# card_base.net
KiCad netlist of a schematic drawn in EAGLE
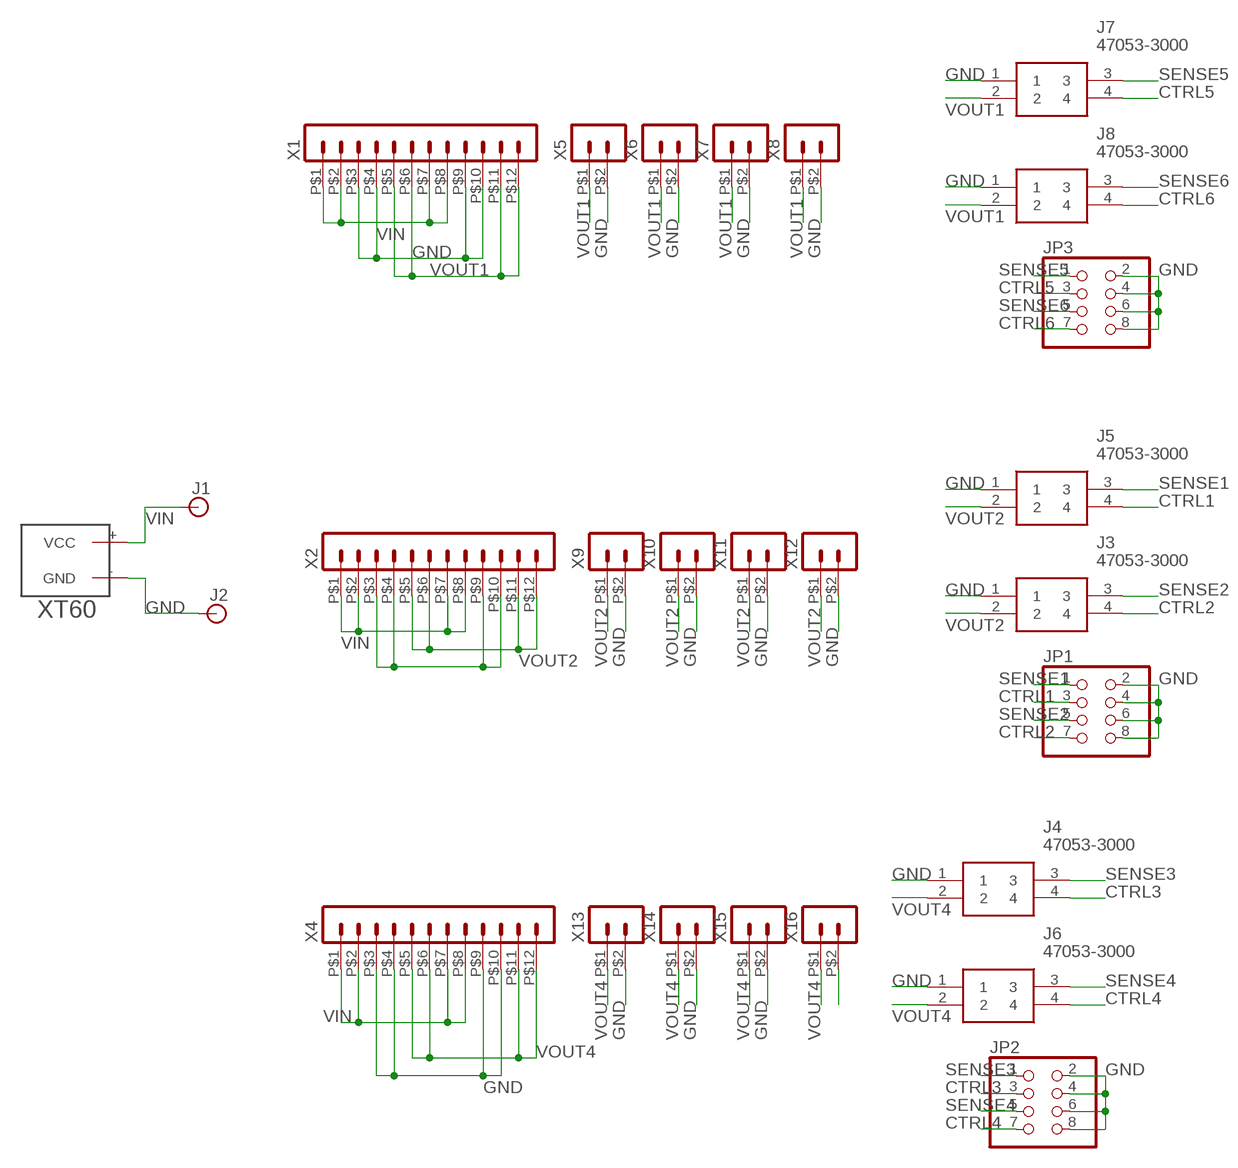
[diagram p0: schematic, sheet 1]

(export (version "E")
  (design (tool "Eeschema 10.0.6"))
  (components
    (comp (ref "J1")
      (value "BANANA_CONN")
      (footprint "eagle-import:BANANA_CONN")
      (libsource (lib "eagle-import") (part "BANANA_CONN"))
    )
    (comp (ref "J2")
      (value "BANANA_CONN")
      (footprint "eagle-import:BANANA_CONN")
      (libsource (lib "eagle-import") (part "BANANA_CONN"))
    )
    (comp (ref "J3")
      (value "47053-3000")
      (footprint "eagle-import:470533000")
      (fields (field (name "MOUSER_PART_NUMBER") "538-47053-3000"))
      (libsource (lib "eagle-import") (part "47053-3000"))
    )
    (comp (ref "J4")
      (value "47053-3000")
      (footprint "eagle-import:470533000")
      (fields (field (name "MOUSER_PART_NUMBER") "538-47053-3000"))
      (libsource (lib "eagle-import") (part "47053-3000"))
    )
    (comp (ref "J5")
      (value "47053-3000")
      (footprint "eagle-import:470533000")
      (fields (field (name "MOUSER_PART_NUMBER") "538-47053-3000"))
      (libsource (lib "eagle-import") (part "47053-3000"))
    )
    (comp (ref "J6")
      (value "47053-3000")
      (footprint "eagle-import:470533000")
      (fields (field (name "MOUSER_PART_NUMBER") "538-47053-3000"))
      (libsource (lib "eagle-import") (part "47053-3000"))
    )
    (comp (ref "J7")
      (value "47053-3000")
      (footprint "eagle-import:470533000")
      (fields (field (name "MOUSER_PART_NUMBER") "538-47053-3000"))
      (libsource (lib "eagle-import") (part "47053-3000"))
    )
    (comp (ref "J8")
      (value "47053-3000")
      (footprint "eagle-import:470533000")
      (fields (field (name "MOUSER_PART_NUMBER") "538-47053-3000"))
      (libsource (lib "eagle-import") (part "47053-3000"))
    )
    (comp (ref "JP1")
      (value "PINHD-2X4")
      (footprint "eagle-import:2X04")
      (libsource (lib "eagle-import") (part "PINHD-2X4"))
    )
    (comp (ref "JP2")
      (value "PINHD-2X4")
      (footprint "eagle-import:2X04")
      (libsource (lib "eagle-import") (part "PINHD-2X4"))
    )
    (comp (ref "JP3")
      (value "PINHD-2X4")
      (footprint "eagle-import:2X04")
      (libsource (lib "eagle-import") (part "PINHD-2X4"))
    )
    (comp (ref "U$1")
      (value "XT60")
      (footprint "eagle-import:XT60")
      (libsource (lib "eagle-import") (part "XT60"))
    )
    (comp (ref "X1")
      (value "HEADER_POS12_44432-1201")
      (footprint "eagle-import:44432-1201")
      (libsource (lib "eagle-import") (part "HEADER_POS12_?44432-1201"))
    )
    (comp (ref "X2")
      (value "HEADER_POS12_44432-1201")
      (footprint "eagle-import:44432-1201")
      (libsource (lib "eagle-import") (part "HEADER_POS12_?44432-1201"))
    )
    (comp (ref "X4")
      (value "HEADER_POS12_44432-1201")
      (footprint "eagle-import:44432-1201")
      (libsource (lib "eagle-import") (part "HEADER_POS12_?44432-1201"))
    )
    (comp (ref "X5")
      (value "HEADER_POS2_44914-0201")
      (footprint "eagle-import:44914-0201")
      (libsource (lib "eagle-import") (part "HEADER_POS2_?44914-0201"))
    )
    (comp (ref "X6")
      (value "HEADER_POS2_44914-0201")
      (footprint "eagle-import:44914-0201")
      (libsource (lib "eagle-import") (part "HEADER_POS2_?44914-0201"))
    )
    (comp (ref "X7")
      (value "HEADER_POS2_44914-0201")
      (footprint "eagle-import:44914-0201")
      (libsource (lib "eagle-import") (part "HEADER_POS2_?44914-0201"))
    )
    (comp (ref "X8")
      (value "HEADER_POS2_44914-0201")
      (footprint "eagle-import:44914-0201")
      (libsource (lib "eagle-import") (part "HEADER_POS2_?44914-0201"))
    )
    (comp (ref "X9")
      (value "HEADER_POS2_44914-0201")
      (footprint "eagle-import:44914-0201")
      (libsource (lib "eagle-import") (part "HEADER_POS2_?44914-0201"))
    )
    (comp (ref "X10")
      (value "HEADER_POS2_44914-0201")
      (footprint "eagle-import:44914-0201")
      (libsource (lib "eagle-import") (part "HEADER_POS2_?44914-0201"))
    )
    (comp (ref "X11")
      (value "HEADER_POS2_44914-0201")
      (footprint "eagle-import:44914-0201")
      (libsource (lib "eagle-import") (part "HEADER_POS2_?44914-0201"))
    )
    (comp (ref "X12")
      (value "HEADER_POS2_44914-0201")
      (footprint "eagle-import:44914-0201")
      (libsource (lib "eagle-import") (part "HEADER_POS2_?44914-0201"))
    )
    (comp (ref "X13")
      (value "HEADER_POS2_44914-0201")
      (footprint "eagle-import:44914-0201")
      (libsource (lib "eagle-import") (part "HEADER_POS2_?44914-0201"))
    )
    (comp (ref "X14")
      (value "HEADER_POS2_44914-0201")
      (footprint "eagle-import:44914-0201")
      (libsource (lib "eagle-import") (part "HEADER_POS2_?44914-0201"))
    )
    (comp (ref "X15")
      (value "HEADER_POS2_44914-0201")
      (footprint "eagle-import:44914-0201")
      (libsource (lib "eagle-import") (part "HEADER_POS2_?44914-0201"))
    )
    (comp (ref "X16")
      (value "HEADER_POS2_44914-0201")
      (footprint "eagle-import:44914-0201")
      (libsource (lib "eagle-import") (part "HEADER_POS2_?44914-0201"))
    )
  )
  (nets
    (net (code "1") (name "/CTRL1") (class "Default")
      (node (ref "J5") (pin "4") (pinfunction "4_4") (pintype "bidirectional"))
      (node (ref "JP1") (pin "3") (pinfunction "3_3") (pintype "passive"))
    )
    (net (code "2") (name "/CTRL2") (class "Default")
      (node (ref "J3") (pin "4") (pinfunction "4_4") (pintype "bidirectional"))
      (node (ref "JP1") (pin "7") (pinfunction "7_7") (pintype "passive"))
    )
    (net (code "3") (name "/CTRL3") (class "Default")
      (node (ref "J4") (pin "4") (pinfunction "4_4") (pintype "bidirectional"))
      (node (ref "JP2") (pin "3") (pinfunction "3_3") (pintype "passive"))
    )
    (net (code "4") (name "/CTRL4") (class "Default")
      (node (ref "J6") (pin "4") (pinfunction "4_4") (pintype "bidirectional"))
      (node (ref "JP2") (pin "7") (pinfunction "7_7") (pintype "passive"))
    )
    (net (code "5") (name "/CTRL5") (class "Default")
      (node (ref "J7") (pin "4") (pinfunction "4_4") (pintype "bidirectional"))
      (node (ref "JP3") (pin "3") (pinfunction "3_3") (pintype "passive"))
    )
    (net (code "6") (name "/CTRL6") (class "Default")
      (node (ref "J8") (pin "4") (pinfunction "4_4") (pintype "bidirectional"))
      (node (ref "JP3") (pin "7") (pinfunction "7_7") (pintype "passive"))
    )
    (net (code "7") (name "/GND") (class "Default")
      (node (ref "J2") (pin "P$1") (pinfunction "1_P$1") (pintype "passive"))
      (node (ref "J3") (pin "1") (pinfunction "1_1") (pintype "bidirectional"))
      (node (ref "J4") (pin "1") (pinfunction "1_1") (pintype "bidirectional"))
      (node (ref "J5") (pin "1") (pinfunction "1_1") (pintype "bidirectional"))
      (node (ref "J6") (pin "1") (pinfunction "1_1") (pintype "bidirectional"))
      (node (ref "J7") (pin "1") (pinfunction "1_1") (pintype "bidirectional"))
      (node (ref "J8") (pin "1") (pinfunction "1_1") (pintype "bidirectional"))
      (node (ref "JP1") (pin "2") (pinfunction "2_2") (pintype "passive"))
      (node (ref "JP1") (pin "4") (pinfunction "4_4") (pintype "passive"))
      (node (ref "JP1") (pin "6") (pinfunction "6_6") (pintype "passive"))
      (node (ref "JP1") (pin "8") (pinfunction "8_8") (pintype "passive"))
      (node (ref "JP2") (pin "2") (pinfunction "2_2") (pintype "passive"))
      (node (ref "JP2") (pin "4") (pinfunction "4_4") (pintype "passive"))
      (node (ref "JP2") (pin "6") (pinfunction "6_6") (pintype "passive"))
      (node (ref "JP2") (pin "8") (pinfunction "8_8") (pintype "passive"))
      (node (ref "JP3") (pin "2") (pinfunction "2_2") (pintype "passive"))
      (node (ref "JP3") (pin "4") (pinfunction "4_4") (pintype "passive"))
      (node (ref "JP3") (pin "6") (pinfunction "6_6") (pintype "passive"))
      (node (ref "JP3") (pin "8") (pinfunction "8_8") (pintype "passive"))
      (node (ref "U$1") (pin "-") (pinfunction "GND_-") (pintype "bidirectional"))
      (node (ref "X1") (pin "P$10") (pinfunction "10_P$10") (pintype "passive"))
      (node (ref "X1") (pin "P$3") (pinfunction "3_P$3") (pintype "passive"))
      (node (ref "X1") (pin "P$4") (pinfunction "4_P$4") (pintype "passive"))
      (node (ref "X1") (pin "P$9") (pinfunction "9_P$9") (pintype "passive"))
      (node (ref "X10") (pin "P$2") (pinfunction "2_P$2") (pintype "passive"))
      (node (ref "X11") (pin "P$2") (pinfunction "2_P$2") (pintype "passive"))
      (node (ref "X12") (pin "P$2") (pinfunction "2_P$2") (pintype "passive"))
      (node (ref "X13") (pin "P$2") (pinfunction "2_P$2") (pintype "passive"))
      (node (ref "X14") (pin "P$2") (pinfunction "2_P$2") (pintype "passive"))
      (node (ref "X15") (pin "P$2") (pinfunction "2_P$2") (pintype "passive"))
      (node (ref "X16") (pin "P$2") (pinfunction "2_P$2") (pintype "passive"))
      (node (ref "X2") (pin "P$10") (pinfunction "10_P$10") (pintype "passive"))
      (node (ref "X2") (pin "P$3") (pinfunction "3_P$3") (pintype "passive"))
      (node (ref "X2") (pin "P$4") (pinfunction "4_P$4") (pintype "passive"))
      (node (ref "X2") (pin "P$9") (pinfunction "9_P$9") (pintype "passive"))
      (node (ref "X4") (pin "P$10") (pinfunction "10_P$10") (pintype "passive"))
      (node (ref "X4") (pin "P$3") (pinfunction "3_P$3") (pintype "passive"))
      (node (ref "X4") (pin "P$4") (pinfunction "4_P$4") (pintype "passive"))
      (node (ref "X4") (pin "P$9") (pinfunction "9_P$9") (pintype "passive"))
      (node (ref "X5") (pin "P$2") (pinfunction "2_P$2") (pintype "passive"))
      (node (ref "X6") (pin "P$2") (pinfunction "2_P$2") (pintype "passive"))
      (node (ref "X7") (pin "P$2") (pinfunction "2_P$2") (pintype "passive"))
      (node (ref "X8") (pin "P$2") (pinfunction "2_P$2") (pintype "passive"))
      (node (ref "X9") (pin "P$2") (pinfunction "2_P$2") (pintype "passive"))
    )
    (net (code "8") (name "/SENSE1") (class "Default")
      (node (ref "J5") (pin "3") (pinfunction "3_3") (pintype "bidirectional"))
      (node (ref "JP1") (pin "1") (pinfunction "1_1") (pintype "passive"))
    )
    (net (code "9") (name "/SENSE2") (class "Default")
      (node (ref "J3") (pin "3") (pinfunction "3_3") (pintype "bidirectional"))
      (node (ref "JP1") (pin "5") (pinfunction "5_5") (pintype "passive"))
    )
    (net (code "10") (name "/SENSE3") (class "Default")
      (node (ref "J4") (pin "3") (pinfunction "3_3") (pintype "bidirectional"))
      (node (ref "JP2") (pin "1") (pinfunction "1_1") (pintype "passive"))
    )
    (net (code "11") (name "/SENSE4") (class "Default")
      (node (ref "J6") (pin "3") (pinfunction "3_3") (pintype "bidirectional"))
      (node (ref "JP2") (pin "5") (pinfunction "5_5") (pintype "passive"))
    )
    (net (code "12") (name "/SENSE5") (class "Default")
      (node (ref "J7") (pin "3") (pinfunction "3_3") (pintype "bidirectional"))
      (node (ref "JP3") (pin "1") (pinfunction "1_1") (pintype "passive"))
    )
    (net (code "13") (name "/SENSE6") (class "Default")
      (node (ref "J8") (pin "3") (pinfunction "3_3") (pintype "bidirectional"))
      (node (ref "JP3") (pin "5") (pinfunction "5_5") (pintype "passive"))
    )
    (net (code "14") (name "/VIN") (class "Default")
      (node (ref "J1") (pin "P$1") (pinfunction "1_P$1") (pintype "passive"))
      (node (ref "U$1") (pin "+") (pinfunction "VCC_+") (pintype "bidirectional"))
      (node (ref "X1") (pin "P$1") (pinfunction "1_P$1") (pintype "passive"))
      (node (ref "X1") (pin "P$2") (pinfunction "2_P$2") (pintype "passive"))
      (node (ref "X1") (pin "P$7") (pinfunction "7_P$7") (pintype "passive"))
      (node (ref "X1") (pin "P$8") (pinfunction "8_P$8") (pintype "passive"))
      (node (ref "X2") (pin "P$1") (pinfunction "1_P$1") (pintype "passive"))
      (node (ref "X2") (pin "P$2") (pinfunction "2_P$2") (pintype "passive"))
      (node (ref "X2") (pin "P$7") (pinfunction "7_P$7") (pintype "passive"))
      (node (ref "X2") (pin "P$8") (pinfunction "8_P$8") (pintype "passive"))
      (node (ref "X4") (pin "P$1") (pinfunction "1_P$1") (pintype "passive"))
      (node (ref "X4") (pin "P$2") (pinfunction "2_P$2") (pintype "passive"))
      (node (ref "X4") (pin "P$7") (pinfunction "7_P$7") (pintype "passive"))
      (node (ref "X4") (pin "P$8") (pinfunction "8_P$8") (pintype "passive"))
    )
    (net (code "15") (name "/VOUT1") (class "Default")
      (node (ref "J7") (pin "2") (pinfunction "2_2") (pintype "bidirectional"))
      (node (ref "J8") (pin "2") (pinfunction "2_2") (pintype "bidirectional"))
      (node (ref "X1") (pin "P$11") (pinfunction "11_P$11") (pintype "passive"))
      (node (ref "X1") (pin "P$12") (pinfunction "12_P$12") (pintype "passive"))
      (node (ref "X1") (pin "P$5") (pinfunction "5_P$5") (pintype "passive"))
      (node (ref "X1") (pin "P$6") (pinfunction "6_P$6") (pintype "passive"))
      (node (ref "X5") (pin "P$1") (pinfunction "1_P$1") (pintype "passive"))
      (node (ref "X6") (pin "P$1") (pinfunction "1_P$1") (pintype "passive"))
      (node (ref "X7") (pin "P$1") (pinfunction "1_P$1") (pintype "passive"))
      (node (ref "X8") (pin "P$1") (pinfunction "1_P$1") (pintype "passive"))
    )
    (net (code "16") (name "/VOUT2") (class "Default")
      (node (ref "J3") (pin "2") (pinfunction "2_2") (pintype "bidirectional"))
      (node (ref "J5") (pin "2") (pinfunction "2_2") (pintype "bidirectional"))
      (node (ref "X10") (pin "P$1") (pinfunction "1_P$1") (pintype "passive"))
      (node (ref "X11") (pin "P$1") (pinfunction "1_P$1") (pintype "passive"))
      (node (ref "X12") (pin "P$1") (pinfunction "1_P$1") (pintype "passive"))
      (node (ref "X2") (pin "P$11") (pinfunction "11_P$11") (pintype "passive"))
      (node (ref "X2") (pin "P$12") (pinfunction "12_P$12") (pintype "passive"))
      (node (ref "X2") (pin "P$5") (pinfunction "5_P$5") (pintype "passive"))
      (node (ref "X2") (pin "P$6") (pinfunction "6_P$6") (pintype "passive"))
      (node (ref "X9") (pin "P$1") (pinfunction "1_P$1") (pintype "passive"))
    )
    (net (code "17") (name "/VOUT4") (class "Default")
      (node (ref "J4") (pin "2") (pinfunction "2_2") (pintype "bidirectional"))
      (node (ref "J6") (pin "2") (pinfunction "2_2") (pintype "bidirectional"))
      (node (ref "X13") (pin "P$1") (pinfunction "1_P$1") (pintype "passive"))
      (node (ref "X14") (pin "P$1") (pinfunction "1_P$1") (pintype "passive"))
      (node (ref "X15") (pin "P$1") (pinfunction "1_P$1") (pintype "passive"))
      (node (ref "X16") (pin "P$1") (pinfunction "1_P$1") (pintype "passive"))
      (node (ref "X4") (pin "P$11") (pinfunction "11_P$11") (pintype "passive"))
      (node (ref "X4") (pin "P$12") (pinfunction "12_P$12") (pintype "passive"))
      (node (ref "X4") (pin "P$5") (pinfunction "5_P$5") (pintype "passive"))
      (node (ref "X4") (pin "P$6") (pinfunction "6_P$6") (pintype "passive"))
    )
  )
)
